# ProProject__20210517_2024-08-10.net
KiCad netlist of a schematic drawn in EasyEDA Pro
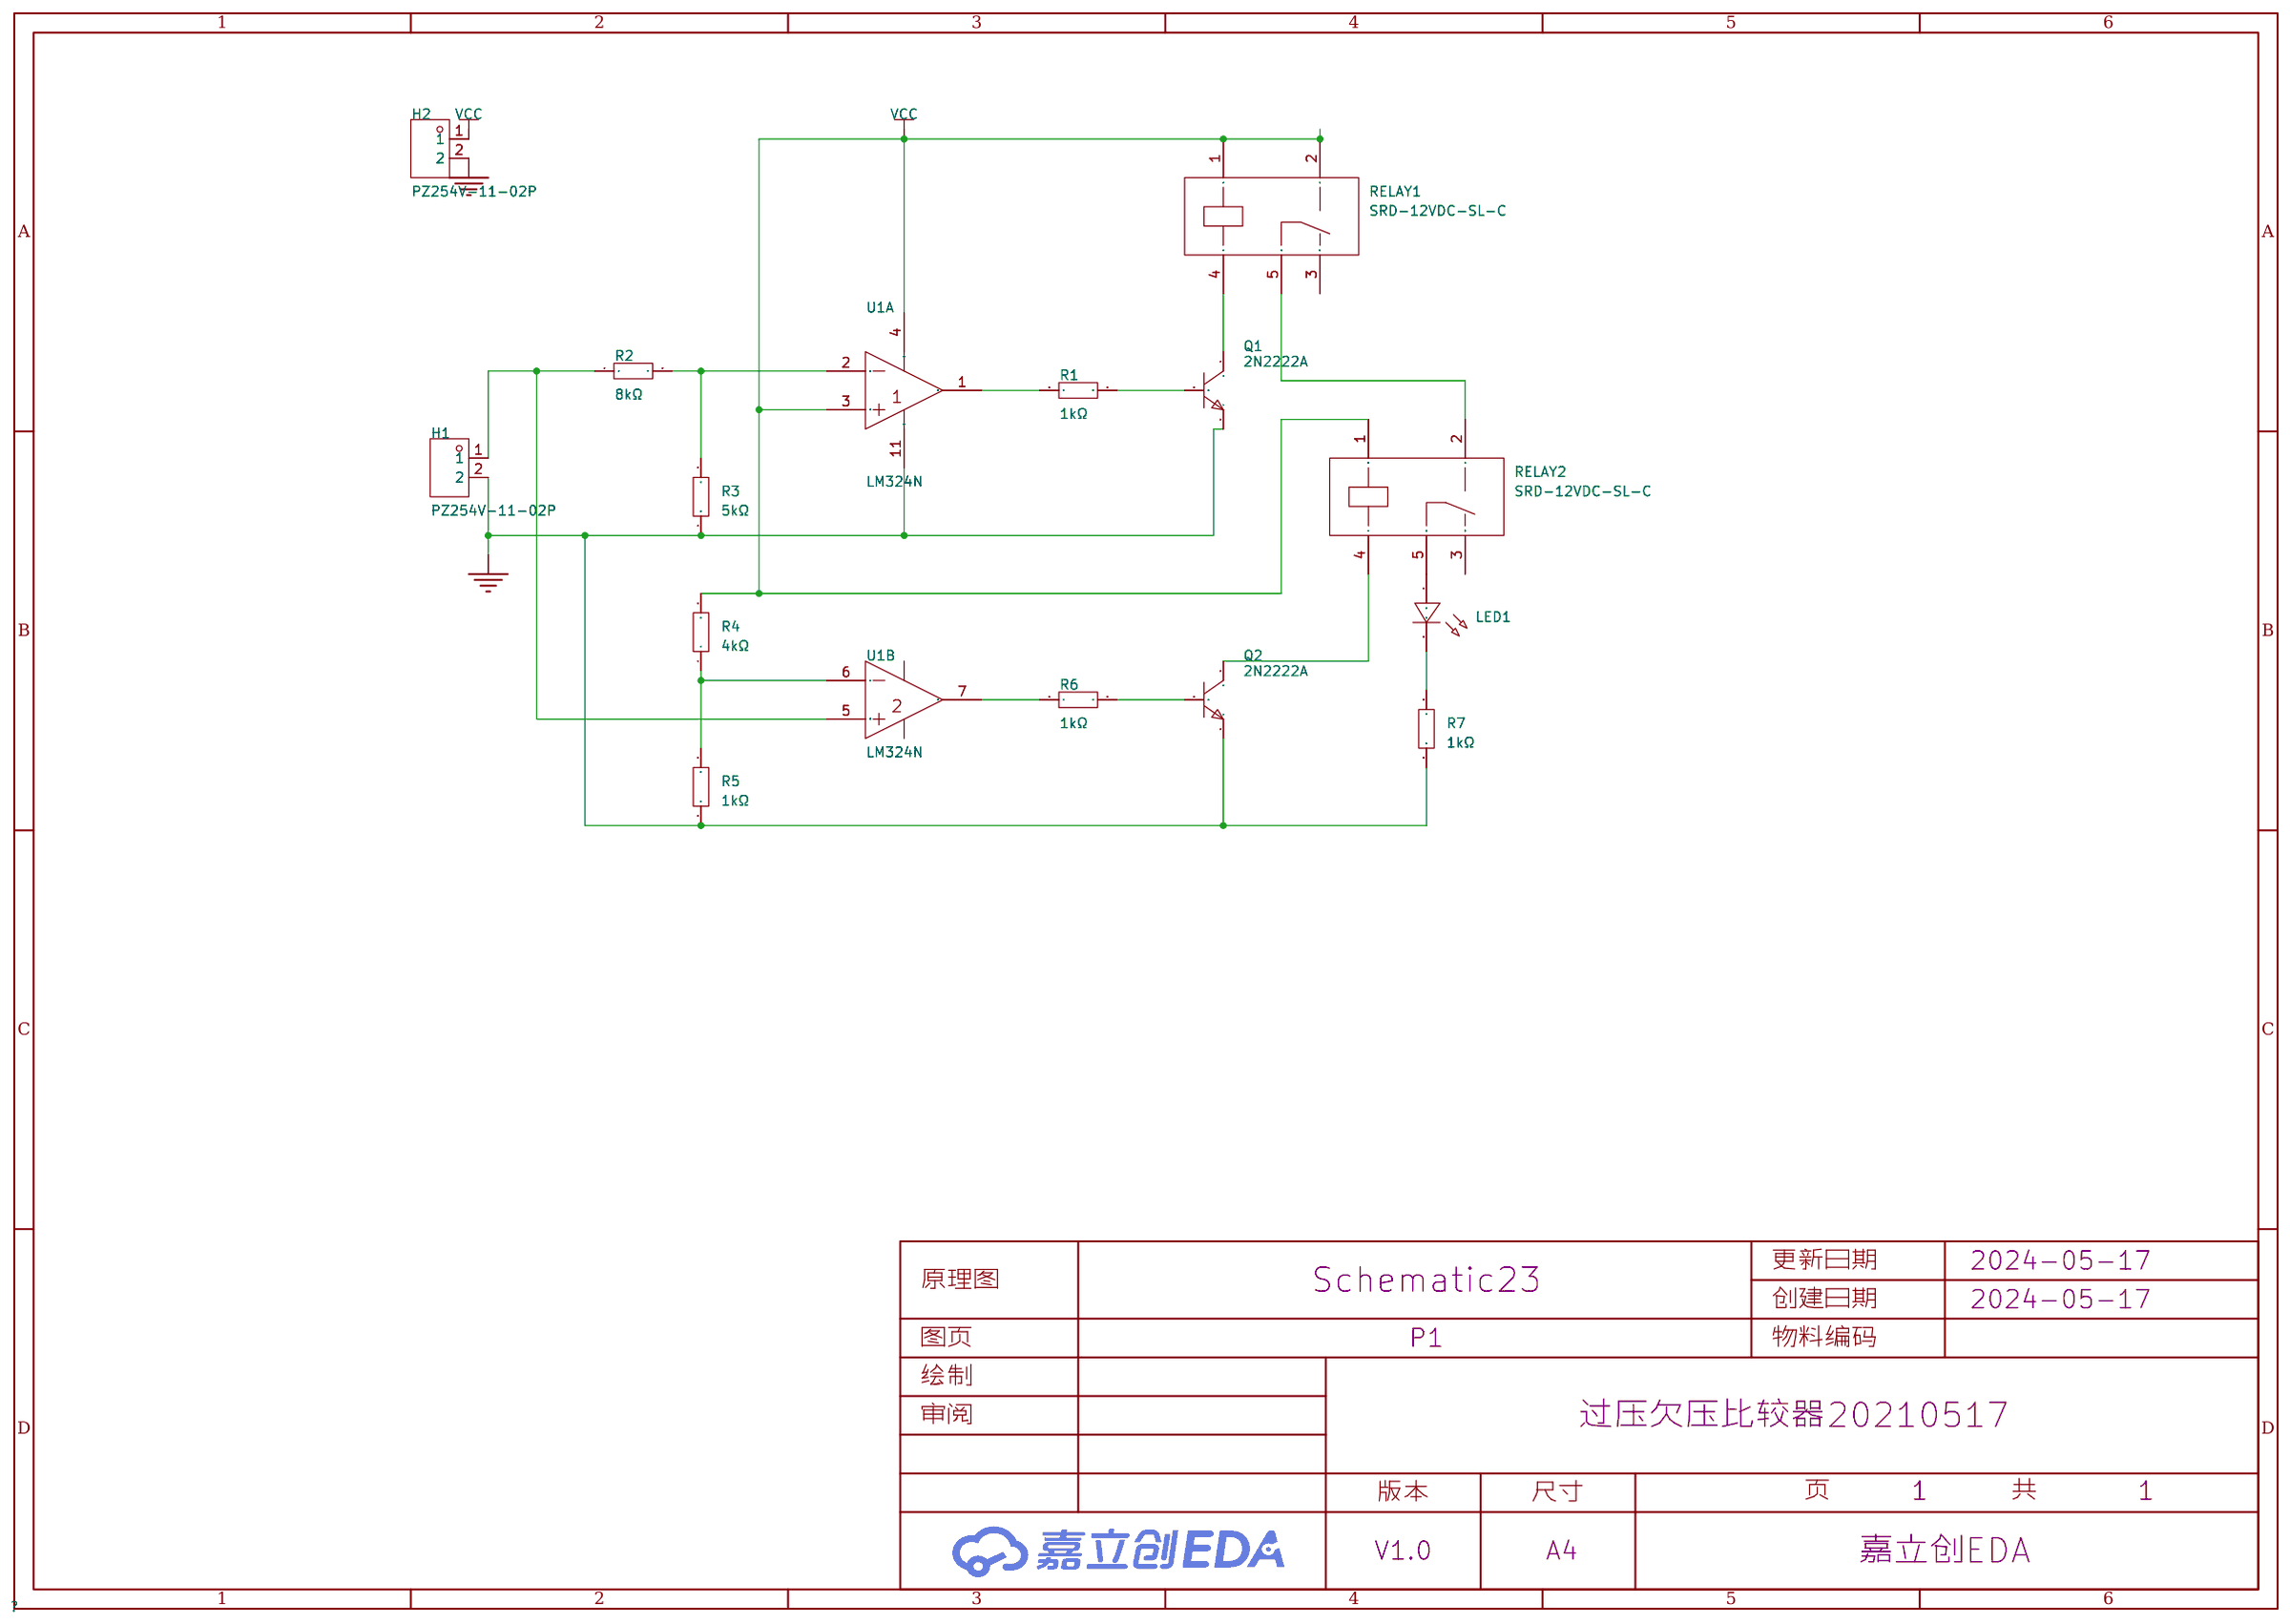
[diagram p0: schematic sheet]

(export (version "E")
  (design (tool "Eeschema 10.0.6"))
  (components
    (comp (ref "H1")
      (value "PZ254V-11-02P")
      (footprint "easyedapro:HDR-TH_2P-P2.54-V-M")
      (fields (field (name "Manufacturer") "XFCN(兴飞)"))
      (libsource (lib "easyedapro") (part "PZ254V-11-02P"))
    )
    (comp (ref "H2")
      (value "PZ254V-11-02P")
      (footprint "easyedapro:HDR-TH_2P-P2.54-V-M")
      (fields (field (name "Manufacturer") "XFCN(兴飞)"))
      (libsource (lib "easyedapro") (part "PZ254V-11-02P"))
    )
    (comp (ref "LED1")
      (value "~")
      (footprint "easyedapro:LED_TH-3mm")
      (libsource (lib "easyedapro") (part "LED_TH-R"))
    )
    (comp (ref "Q1")
      (value "2N2222A")
      (footprint "easyedapro:TO-92-3_L4.8-W3.7-P2.54-R")
      (description "晶体管类型:NPN;集电极电流(Ic):600mA;集射极击穿电压(Vceo):40V;功率(Pd):625mW;直流电流增益(hFE@Ic,Vce):100@150mA,10V;")
      (fields (field (name "Manufacturer") "BLUE ROCKET(蓝箭)"))
      (libsource (lib "easyedapro") (part "2N2222A"))
    )
    (comp (ref "Q2")
      (value "2N2222A")
      (footprint "easyedapro:TO-92-3_L4.8-W3.7-P2.54-R")
      (description "晶体管类型:NPN;集电极电流(Ic):600mA;集射极击穿电压(Vceo):40V;功率(Pd):625mW;直流电流增益(hFE@Ic,Vce):100@150mA,10V;")
      (fields (field (name "Manufacturer") "BLUE ROCKET(蓝箭)"))
      (libsource (lib "easyedapro") (part "2N2222A"))
    )
    (comp (ref "R1")
      (value "1kΩ")
      (footprint "easyedapro:Res_1/8W")
      (libsource (lib "easyedapro") (part "电阻"))
    )
    (comp (ref "R2")
      (value "8kΩ")
      (footprint "easyedapro:Res_1/8W")
      (libsource (lib "easyedapro") (part "电阻"))
    )
    (comp (ref "R3")
      (value "5kΩ")
      (footprint "easyedapro:Res_1/8W")
      (libsource (lib "easyedapro") (part "电阻"))
    )
    (comp (ref "R4")
      (value "4kΩ")
      (footprint "easyedapro:Res_1/8W")
      (libsource (lib "easyedapro") (part "电阻"))
    )
    (comp (ref "R5")
      (value "1kΩ")
      (footprint "easyedapro:Res_1/8W")
      (libsource (lib "easyedapro") (part "电阻"))
    )
    (comp (ref "R6")
      (value "1kΩ")
      (footprint "easyedapro:Res_1/8W")
      (libsource (lib "easyedapro") (part "电阻"))
    )
    (comp (ref "R7")
      (value "1kΩ")
      (footprint "easyedapro:Res_1/8W")
      (libsource (lib "easyedapro") (part "电阻"))
    )
    (comp (ref "RELAY1")
      (value "SRD-12VDC-SL-C")
      (footprint "easyedapro:RELAY-TH_SRD-XXVDC-XL-C")
      (description "线圈电压:12V;触点形式:一组转换:1C(单刀双掷-转换);触点容量(电阻负载):-;最大切换电压:250V@AC;最大切换电流:15A;")
      (fields (field (name "Manufacturer") "松乐"))
      (libsource (lib "easyedapro") (part "SRD-12VDC-SL-C"))
    )
    (comp (ref "RELAY2")
      (value "SRD-12VDC-SL-C")
      (footprint "easyedapro:RELAY-TH_SRD-XXVDC-XL-C")
      (description "线圈电压:12V;触点形式:一组转换:1C(单刀双掷-转换);触点容量(电阻负载):-;最大切换电压:250V@AC;最大切换电流:15A;")
      (fields (field (name "Manufacturer") "松乐"))
      (libsource (lib "easyedapro") (part "SRD-12VDC-SL-C"))
    )
    (comp (ref "U1")
      (value "LM324N")
      (footprint "easyedapro:DIP-14_L19.4-W6.4-P2.54-LS7.6-BL")
      (description "放大器数:-;")
      (fields (field (name "Manufacturer") "HGSEMI(华冠)"))
      (libsource (lib "easyedapro") (part "LM324N_C725320"))
    )
  )
  (nets
    (net (code "1") (name "GND") (class "Default")
      (node (ref "H1") (pin "2") (pinfunction "2_2") (pintype "unspecified"))
      (node (ref "H2") (pin "2") (pinfunction "2_2") (pintype "unspecified"))
      (node (ref "Q1") (pin "3") (pinfunction "E_3") (pintype "unspecified"))
      (node (ref "Q2") (pin "3") (pinfunction "E_3") (pintype "unspecified"))
      (node (ref "R3") (pin "1") (pinfunction "1_1") (pintype "input"))
      (node (ref "R5") (pin "1") (pinfunction "1_1") (pintype "input"))
      (node (ref "R7") (pin "1") (pinfunction "1_1") (pintype "input"))
      (node (ref "U1") (pin "11") (pinfunction "GND_11") (pintype "unspecified"))
    )
    (net (code "2") (name "Net-(LED1-A)") (class "Default")
      (node (ref "LED1") (pin "2") (pinfunction "A_2") (pintype "input"))
      (node (ref "R7") (pin "2") (pinfunction "2_2") (pintype "input"))
    )
    (net (code "3") (name "Net-(LED1-C)") (class "Default")
      (node (ref "LED1") (pin "1") (pinfunction "C_1") (pintype "input"))
      (node (ref "RELAY2") (pin "5") (pinfunction "5_5") (pintype "input"))
    )
    (net (code "4") (name "Net-(Q1-B)") (class "Default")
      (node (ref "Q1") (pin "2") (pinfunction "B_2") (pintype "unspecified"))
      (node (ref "R1") (pin "2") (pinfunction "2_2") (pintype "input"))
    )
    (net (code "5") (name "Net-(Q1-C)") (class "Default")
      (node (ref "Q1") (pin "1") (pinfunction "C_1") (pintype "unspecified"))
      (node (ref "RELAY1") (pin "4") (pinfunction "4_4") (pintype "input"))
    )
    (net (code "6") (name "Net-(Q2-B)") (class "Default")
      (node (ref "Q2") (pin "2") (pinfunction "B_2") (pintype "unspecified"))
      (node (ref "R6") (pin "2") (pinfunction "2_2") (pintype "input"))
    )
    (net (code "7") (name "Net-(Q2-C)") (class "Default")
      (node (ref "Q2") (pin "1") (pinfunction "C_1") (pintype "unspecified"))
      (node (ref "RELAY2") (pin "4") (pinfunction "4_4") (pintype "input"))
    )
    (net (code "8") (name "Net-(RELAY1-Pad5)") (class "Default")
      (node (ref "RELAY1") (pin "5") (pinfunction "5_5") (pintype "input"))
      (node (ref "RELAY2") (pin "2") (pinfunction "2_2") (pintype "input"))
    )
    (net (code "9") (name "Net-(U1A-IN1-)") (class "Default")
      (node (ref "R2") (pin "2") (pinfunction "2_2") (pintype "input"))
      (node (ref "R3") (pin "2") (pinfunction "2_2") (pintype "input"))
      (node (ref "U1") (pin "2") (pinfunction "IN1-_2") (pintype "unspecified"))
    )
    (net (code "10") (name "Net-(U1A-OUT1)") (class "Default")
      (node (ref "R1") (pin "1") (pinfunction "1_1") (pintype "input"))
      (node (ref "U1") (pin "1") (pinfunction "OUT1_1") (pintype "output"))
    )
    (net (code "11") (name "Net-(U1B-IN2+)") (class "Default")
      (node (ref "H1") (pin "1") (pinfunction "1_1") (pintype "unspecified"))
      (node (ref "R2") (pin "1") (pinfunction "1_1") (pintype "input"))
      (node (ref "U1") (pin "5") (pinfunction "IN2+_5") (pintype "unspecified"))
    )
    (net (code "12") (name "Net-(U1B-IN2-)") (class "Default")
      (node (ref "R4") (pin "1") (pinfunction "1_1") (pintype "input"))
      (node (ref "R5") (pin "2") (pinfunction "2_2") (pintype "input"))
      (node (ref "U1") (pin "6") (pinfunction "IN2-_6") (pintype "unspecified"))
    )
    (net (code "13") (name "Net-(U1B-OUT2)") (class "Default")
      (node (ref "R6") (pin "1") (pinfunction "1_1") (pintype "input"))
      (node (ref "U1") (pin "7") (pinfunction "OUT2_7") (pintype "output"))
    )
    (net (code "14") (name "VCC") (class "Default")
      (node (ref "H2") (pin "1") (pinfunction "1_1") (pintype "unspecified"))
      (node (ref "R4") (pin "2") (pinfunction "2_2") (pintype "input"))
      (node (ref "RELAY1") (pin "1") (pinfunction "1_1") (pintype "input"))
      (node (ref "RELAY1") (pin "2") (pinfunction "2_2") (pintype "input"))
      (node (ref "RELAY2") (pin "1") (pinfunction "1_1") (pintype "input"))
      (node (ref "U1") (pin "3") (pinfunction "IN1+_3") (pintype "unspecified"))
      (node (ref "U1") (pin "4") (pinfunction "VCC_4") (pintype "unspecified"))
    )
    (net (code "15") (name "unconnected-(RELAY1-Pad3)") (class "Default")
      (node (ref "RELAY1") (pin "3") (pinfunction "3_3") (pintype "input"))
    )
    (net (code "16") (name "unconnected-(RELAY2-Pad3)") (class "Default")
      (node (ref "RELAY2") (pin "3") (pinfunction "3_3") (pintype "input"))
    )
  )
)
